# milligrids_v05_single_board.net
KiCad netlist of a schematic drawn in EAGLE
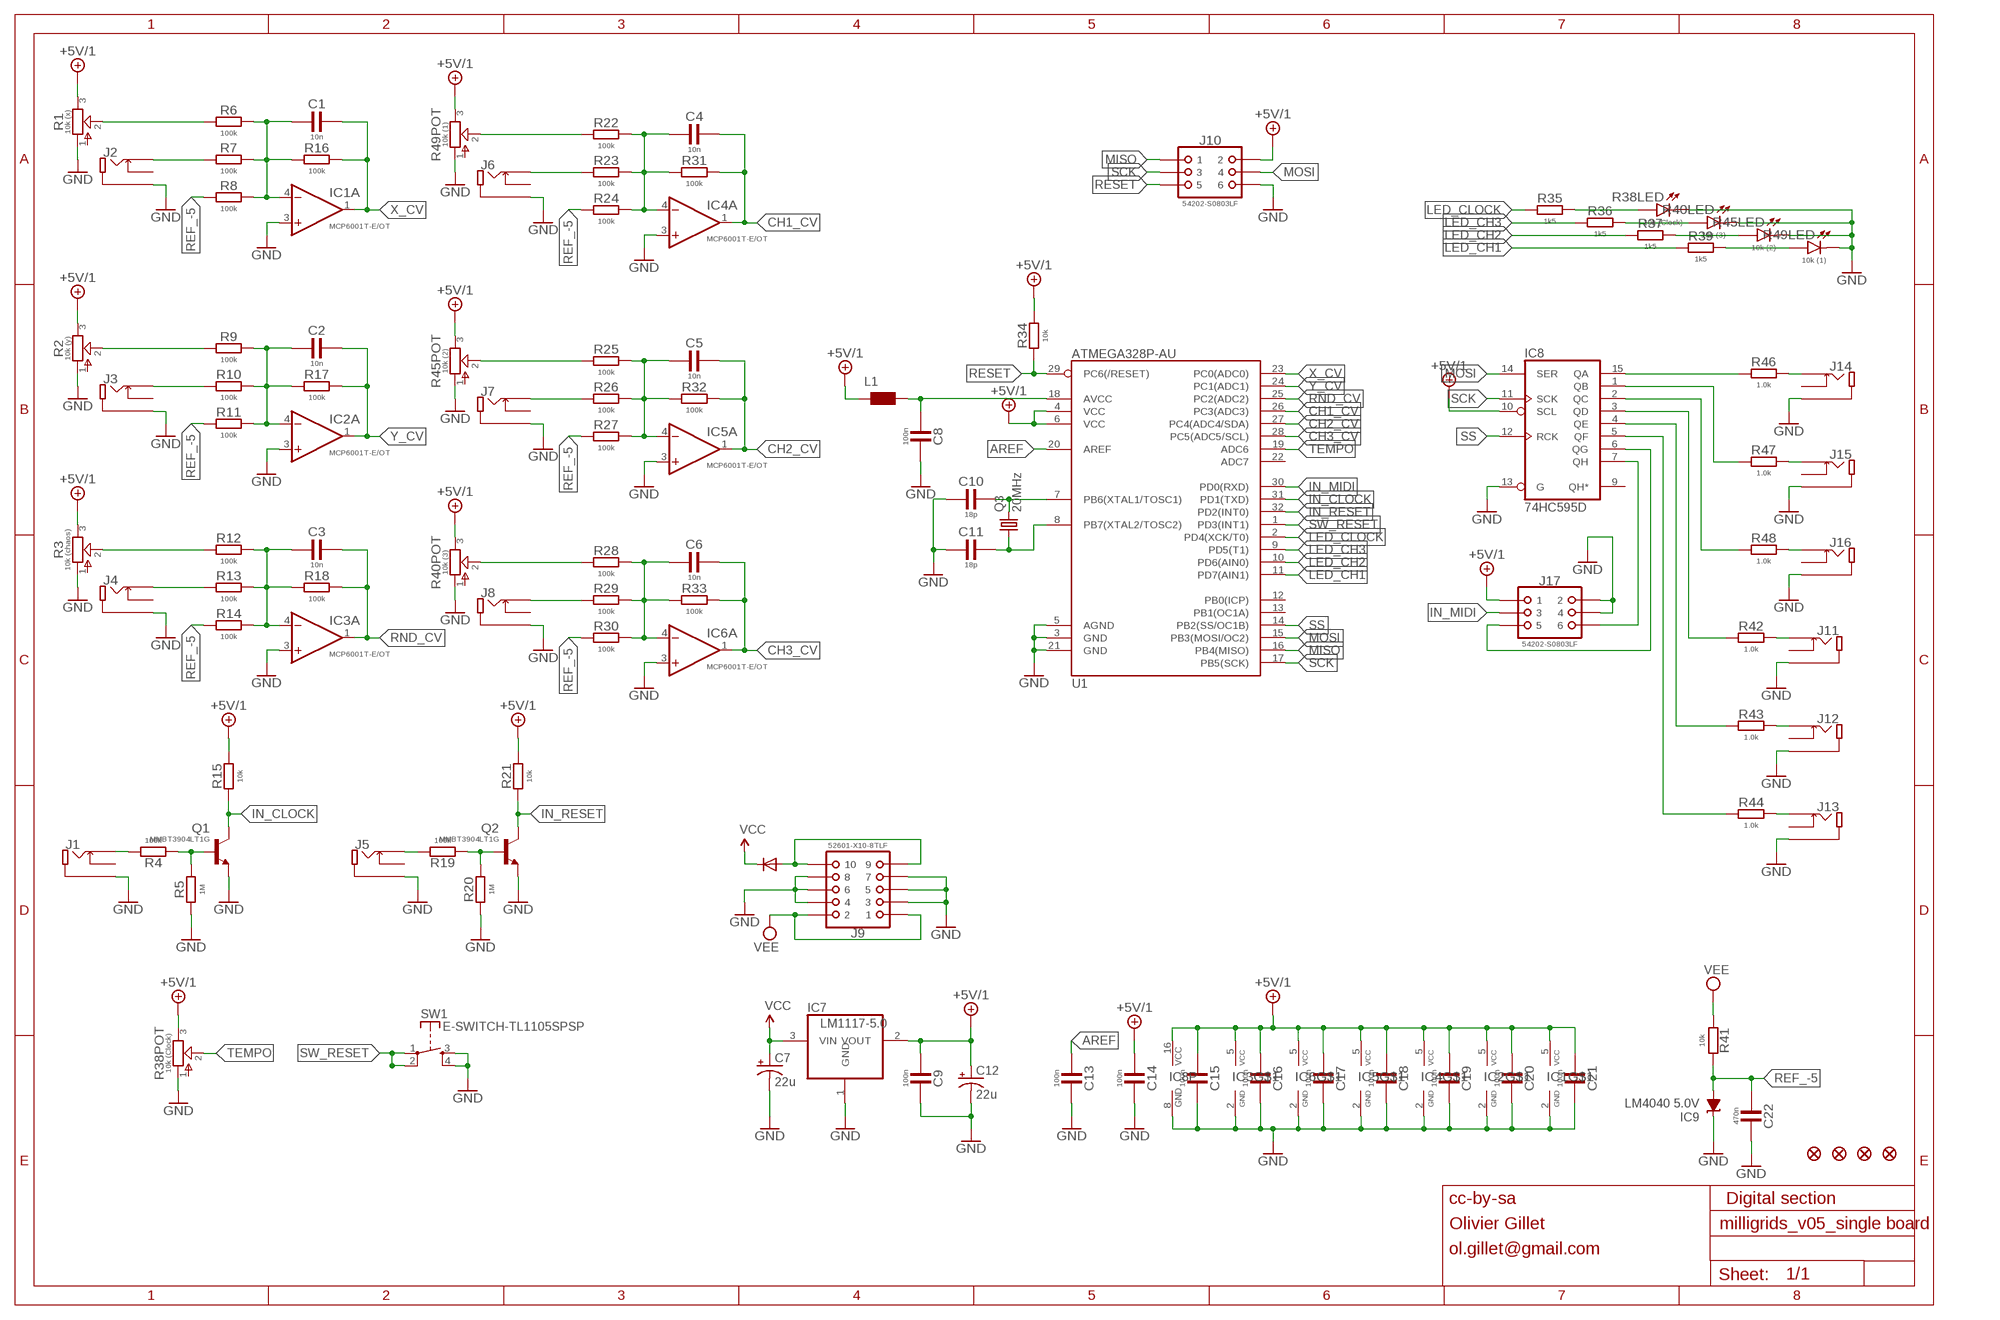
[diagram p0: schematic, sheet 1]

(export (version "E")
  (design (tool "Eeschema 10.0.6"))
  (components
    (comp (ref "C1")
      (value "10n")
      (footprint "eagle-import:C0805")
      (libsource (lib "eagle-import") (part "C0805"))
    )
    (comp (ref "C2")
      (value "10n")
      (footprint "eagle-import:C0805")
      (libsource (lib "eagle-import") (part "C0805"))
    )
    (comp (ref "C3")
      (value "10n")
      (footprint "eagle-import:C0805")
      (libsource (lib "eagle-import") (part "C0805"))
    )
    (comp (ref "C4")
      (value "10n")
      (footprint "eagle-import:C0603")
      (libsource (lib "eagle-import") (part "C0603"))
    )
    (comp (ref "C5")
      (value "10n")
      (footprint "eagle-import:C0603")
      (libsource (lib "eagle-import") (part "C0603"))
    )
    (comp (ref "C6")
      (value "10n")
      (footprint "eagle-import:C0603")
      (libsource (lib "eagle-import") (part "C0603"))
    )
    (comp (ref "C7")
      (value "22u")
      (footprint "eagle-import:PANASONIC_C")
      (libsource (lib "eagle-import") (part "CPOL-USC"))
    )
    (comp (ref "C8")
      (value "100n")
      (footprint "eagle-import:C0805")
      (libsource (lib "eagle-import") (part "C0805"))
    )
    (comp (ref "C9")
      (value "100n")
      (footprint "eagle-import:C0805")
      (libsource (lib "eagle-import") (part "C0805"))
    )
    (comp (ref "C10")
      (value "18p")
      (footprint "eagle-import:C0603")
      (libsource (lib "eagle-import") (part "C0603"))
    )
    (comp (ref "C11")
      (value "18p")
      (footprint "eagle-import:C0603")
      (libsource (lib "eagle-import") (part "C0603"))
    )
    (comp (ref "C12")
      (value "22u")
      (footprint "eagle-import:PANASONIC_C")
      (libsource (lib "eagle-import") (part "CPOL-USC"))
    )
    (comp (ref "C13")
      (value "100n")
      (footprint "eagle-import:C0805")
      (libsource (lib "eagle-import") (part "C0805"))
    )
    (comp (ref "C14")
      (value "100n")
      (footprint "eagle-import:C0805")
      (libsource (lib "eagle-import") (part "C0805"))
    )
    (comp (ref "C15")
      (value "100n")
      (footprint "eagle-import:C0805")
      (libsource (lib "eagle-import") (part "C0805"))
    )
    (comp (ref "C16")
      (value "100n")
      (footprint "eagle-import:C0805")
      (libsource (lib "eagle-import") (part "C0805"))
    )
    (comp (ref "C17")
      (value "100n")
      (footprint "eagle-import:C0805")
      (libsource (lib "eagle-import") (part "C0805"))
    )
    (comp (ref "C18")
      (value "100n")
      (footprint "eagle-import:C0805")
      (libsource (lib "eagle-import") (part "C0805"))
    )
    (comp (ref "C19")
      (value "100n")
      (footprint "eagle-import:C0805")
      (libsource (lib "eagle-import") (part "C0805"))
    )
    (comp (ref "C20")
      (value "100n")
      (footprint "eagle-import:C0805")
      (libsource (lib "eagle-import") (part "C0805"))
    )
    (comp (ref "C21")
      (value "100n")
      (footprint "eagle-import:C0805")
      (libsource (lib "eagle-import") (part "C0805"))
    )
    (comp (ref "C22")
      (value "470n")
      (footprint "eagle-import:C0805")
      (libsource (lib "eagle-import") (part "C0805"))
    )
    (comp (ref "D1")
      (value "1N5819HW")
      (footprint "eagle-import:SOD123")
      (libsource (lib "eagle-import") (part "DIODE-SOD123"))
    )
    (comp (ref "IC1")
      (value "MCP6001T-E/OT")
      (footprint "eagle-import:SOT23-5")
      (libsource (lib "eagle-import") (part "MCP6001T-E/OT"))
    )
    (comp (ref "IC2")
      (value "MCP6001T-E/OT")
      (footprint "eagle-import:SOT23-5")
      (libsource (lib "eagle-import") (part "MCP6001T-E/OT"))
    )
    (comp (ref "IC3")
      (value "MCP6001T-E/OT")
      (footprint "eagle-import:SOT23-5")
      (libsource (lib "eagle-import") (part "MCP6001T-E/OT"))
    )
    (comp (ref "IC4")
      (value "MCP6001T-E/OT")
      (footprint "eagle-import:SOT23-5")
      (libsource (lib "eagle-import") (part "MCP6001T-E/OT"))
    )
    (comp (ref "IC5")
      (value "MCP6001T-E/OT")
      (footprint "eagle-import:SOT23-5")
      (libsource (lib "eagle-import") (part "MCP6001T-E/OT"))
    )
    (comp (ref "IC6")
      (value "MCP6001T-E/OT")
      (footprint "eagle-import:SOT23-5")
      (libsource (lib "eagle-import") (part "MCP6001T-E/OT"))
    )
    (comp (ref "IC7")
      (value "LM1117-5.0")
      (footprint "eagle-import:SOT223")
      (libsource (lib "eagle-import") (part "REG1117"))
    )
    (comp (ref "IC8")
      (value "74HC595D")
      (footprint "eagle-import:SO16")
      (libsource (lib "eagle-import") (part "74595DHC"))
    )
    (comp (ref "IC9")
      (value "LM4040 5.0V")
      (footprint "eagle-import:DBZ_R-PDSO-G3")
      (libsource (lib "eagle-import") (part "LM4041DBZC12"))
    )
    (comp (ref "J1")
      (value "WQP-PJ301M6(THONKICONN)")
      (footprint "eagle-import:WQP-PJ301M6(THONKICONN)")
      (libsource (lib "eagle-import") (part "WQP-PJ301M6(THONKICONN)"))
    )
    (comp (ref "J2")
      (value "WQP-PJ301M6(THONKICONN)")
      (footprint "eagle-import:WQP-PJ301M6(THONKICONN)")
      (libsource (lib "eagle-import") (part "WQP-PJ301M6(THONKICONN)"))
    )
    (comp (ref "J3")
      (value "WQP-PJ301M6(THONKICONN)")
      (footprint "eagle-import:WQP-PJ301M6(THONKICONN)")
      (libsource (lib "eagle-import") (part "WQP-PJ301M6(THONKICONN)"))
    )
    (comp (ref "J4")
      (value "WQP-PJ301M6(THONKICONN)")
      (footprint "eagle-import:WQP-PJ301M6(THONKICONN)")
      (libsource (lib "eagle-import") (part "WQP-PJ301M6(THONKICONN)"))
    )
    (comp (ref "J5")
      (value "WQP-PJ301M6(THONKICONN)")
      (footprint "eagle-import:WQP-PJ301M6(THONKICONN)")
      (libsource (lib "eagle-import") (part "WQP-PJ301M6(THONKICONN)"))
    )
    (comp (ref "J6")
      (value "WQP-PJ301M6(THONKICONN)")
      (footprint "eagle-import:WQP-PJ301M6(THONKICONN)")
      (libsource (lib "eagle-import") (part "WQP-PJ301M6(THONKICONN)"))
    )
    (comp (ref "J7")
      (value "WQP-PJ301M6(THONKICONN)")
      (footprint "eagle-import:WQP-PJ301M6(THONKICONN)")
      (libsource (lib "eagle-import") (part "WQP-PJ301M6(THONKICONN)"))
    )
    (comp (ref "J8")
      (value "WQP-PJ301M6(THONKICONN)")
      (footprint "eagle-import:WQP-PJ301M6(THONKICONN)")
      (libsource (lib "eagle-import") (part "WQP-PJ301M6(THONKICONN)"))
    )
    (comp (ref "J9")
      (value "52601-X10-8TLF")
      (footprint "eagle-import:52601-(X)10-8TLF")
      (libsource (lib "eagle-import") (part "52601-X10-8TLF"))
    )
    (comp (ref "J10")
      (value "54202-S0803LF")
      (footprint "eagle-import:54202-S0803LF")
      (libsource (lib "eagle-import") (part "54202-S0803LF"))
    )
    (comp (ref "J11")
      (value "WQP-PJ301M6(THONKICONN)")
      (footprint "eagle-import:WQP-PJ301M6(THONKICONN)")
      (libsource (lib "eagle-import") (part "WQP-PJ301M6(THONKICONN)"))
    )
    (comp (ref "J12")
      (value "WQP-PJ301M6(THONKICONN)")
      (footprint "eagle-import:WQP-PJ301M6(THONKICONN)")
      (libsource (lib "eagle-import") (part "WQP-PJ301M6(THONKICONN)"))
    )
    (comp (ref "J13")
      (value "WQP-PJ301M6(THONKICONN)")
      (footprint "eagle-import:WQP-PJ301M6(THONKICONN)")
      (libsource (lib "eagle-import") (part "WQP-PJ301M6(THONKICONN)"))
    )
    (comp (ref "J14")
      (value "WQP-PJ301M6(THONKICONN)")
      (footprint "eagle-import:WQP-PJ301M6(THONKICONN)")
      (libsource (lib "eagle-import") (part "WQP-PJ301M6(THONKICONN)"))
    )
    (comp (ref "J15")
      (value "WQP-PJ301M6(THONKICONN)")
      (footprint "eagle-import:WQP-PJ301M6(THONKICONN)")
      (libsource (lib "eagle-import") (part "WQP-PJ301M6(THONKICONN)"))
    )
    (comp (ref "J16")
      (value "WQP-PJ301M6(THONKICONN)")
      (footprint "eagle-import:WQP-PJ301M6(THONKICONN)")
      (libsource (lib "eagle-import") (part "WQP-PJ301M6(THONKICONN)"))
    )
    (comp (ref "J17")
      (value "54202-S0803LF")
      (footprint "eagle-import:54202-S0803LF")
      (libsource (lib "eagle-import") (part "54202-S0803LF"))
    )
    (comp (ref "JP2")
      (value "FIDUCIAL1X2")
      (footprint "eagle-import:FIDUCIAL-1X2")
      (libsource (lib "eagle-import") (part "FIDUCIAL1X2"))
    )
    (comp (ref "JP3")
      (value "FIDUCIAL1X2")
      (footprint "eagle-import:FIDUCIAL-1X2")
      (libsource (lib "eagle-import") (part "FIDUCIAL1X2"))
    )
    (comp (ref "JP4")
      (value "FIDUCIAL1X2")
      (footprint "eagle-import:FIDUCIAL-1X2")
      (libsource (lib "eagle-import") (part "FIDUCIAL1X2"))
    )
    (comp (ref "JP5")
      (value "FIDUCIAL1X2")
      (footprint "eagle-import:FIDUCIAL-1X2")
      (libsource (lib "eagle-import") (part "FIDUCIAL1X2"))
    )
    (comp (ref "L1")
      (value "WE-CBF_0603")
      (footprint "eagle-import:0603")
      (libsource (lib "eagle-import") (part "WE-CBF_0603"))
    )
    (comp (ref "Q1")
      (value "MMBT3904LT1G")
      (footprint "eagle-import:SOT23-3")
      (libsource (lib "eagle-import") (part "MMBT3904LT1G"))
    )
    (comp (ref "Q2")
      (value "MMBT3904LT1G")
      (footprint "eagle-import:SOT23-3")
      (libsource (lib "eagle-import") (part "MMBT3904LT1G"))
    )
    (comp (ref "Q3")
      (value "20MHz")
      (footprint "eagle-import:HC49UP")
      (libsource (lib "eagle-import") (part "CRYSTALHC49UP"))
    )
    (comp (ref "R1")
      (value "10k (x)")
      (footprint "eagle-import:SONGHUEI-RK0914")
      (libsource (lib "eagle-import") (part "SONGHUEI-RK0914"))
    )
    (comp (ref "R2")
      (value "10k (y)")
      (footprint "eagle-import:SONGHUEI-RK0914")
      (libsource (lib "eagle-import") (part "SONGHUEI-RK0914"))
    )
    (comp (ref "R3")
      (value "10k (chaos)")
      (footprint "eagle-import:SONGHUEI-RK0914")
      (libsource (lib "eagle-import") (part "SONGHUEI-RK0914"))
    )
    (comp (ref "R4")
      (value "100k")
      (footprint "eagle-import:R0603")
      (libsource (lib "eagle-import") (part "R0603"))
    )
    (comp (ref "R5")
      (value "1M")
      (footprint "eagle-import:R0603")
      (libsource (lib "eagle-import") (part "R0603"))
    )
    (comp (ref "R6")
      (value "100k")
      (footprint "eagle-import:R0603")
      (libsource (lib "eagle-import") (part "R0603"))
    )
    (comp (ref "R7")
      (value "100k")
      (footprint "eagle-import:R0603")
      (libsource (lib "eagle-import") (part "R0603"))
    )
    (comp (ref "R8")
      (value "100k")
      (footprint "eagle-import:R0603")
      (libsource (lib "eagle-import") (part "R0603"))
    )
    (comp (ref "R9")
      (value "100k")
      (footprint "eagle-import:R0603")
      (libsource (lib "eagle-import") (part "R0603"))
    )
    (comp (ref "R10")
      (value "100k")
      (footprint "eagle-import:R0603")
      (libsource (lib "eagle-import") (part "R0603"))
    )
    (comp (ref "R11")
      (value "100k")
      (footprint "eagle-import:R0603")
      (libsource (lib "eagle-import") (part "R0603"))
    )
    (comp (ref "R12")
      (value "100k")
      (footprint "eagle-import:R0603")
      (libsource (lib "eagle-import") (part "R0603"))
    )
    (comp (ref "R13")
      (value "100k")
      (footprint "eagle-import:R0603")
      (libsource (lib "eagle-import") (part "R0603"))
    )
    (comp (ref "R14")
      (value "100k")
      (footprint "eagle-import:R0603")
      (libsource (lib "eagle-import") (part "R0603"))
    )
    (comp (ref "R15")
      (value "10k")
      (footprint "eagle-import:R0805")
      (libsource (lib "eagle-import") (part "R0805"))
    )
    (comp (ref "R16")
      (value "100k")
      (footprint "eagle-import:R0603")
      (libsource (lib "eagle-import") (part "R0603"))
    )
    (comp (ref "R17")
      (value "100k")
      (footprint "eagle-import:R0603")
      (libsource (lib "eagle-import") (part "R0603"))
    )
    (comp (ref "R18")
      (value "100k")
      (footprint "eagle-import:R0603")
      (libsource (lib "eagle-import") (part "R0603"))
    )
    (comp (ref "R19")
      (value "100k")
      (footprint "eagle-import:R0603")
      (libsource (lib "eagle-import") (part "R0603"))
    )
    (comp (ref "R20")
      (value "1M")
      (footprint "eagle-import:R0603")
      (libsource (lib "eagle-import") (part "R0603"))
    )
    (comp (ref "R21")
      (value "10k")
      (footprint "eagle-import:R0805")
      (libsource (lib "eagle-import") (part "R0805"))
    )
    (comp (ref "R22")
      (value "100k")
      (footprint "eagle-import:R0603")
      (libsource (lib "eagle-import") (part "R0603"))
    )
    (comp (ref "R23")
      (value "100k")
      (footprint "eagle-import:R0603")
      (libsource (lib "eagle-import") (part "R0603"))
    )
    (comp (ref "R24")
      (value "100k")
      (footprint "eagle-import:R0603")
      (libsource (lib "eagle-import") (part "R0603"))
    )
    (comp (ref "R25")
      (value "100k")
      (footprint "eagle-import:R0603")
      (libsource (lib "eagle-import") (part "R0603"))
    )
    (comp (ref "R26")
      (value "100k")
      (footprint "eagle-import:R0603")
      (libsource (lib "eagle-import") (part "R0603"))
    )
    (comp (ref "R27")
      (value "100k")
      (footprint "eagle-import:R0603")
      (libsource (lib "eagle-import") (part "R0603"))
    )
    (comp (ref "R28")
      (value "100k")
      (footprint "eagle-import:R0603")
      (libsource (lib "eagle-import") (part "R0603"))
    )
    (comp (ref "R29")
      (value "100k")
      (footprint "eagle-import:R0603")
      (libsource (lib "eagle-import") (part "R0603"))
    )
    (comp (ref "R30")
      (value "100k")
      (footprint "eagle-import:R0603")
      (libsource (lib "eagle-import") (part "R0603"))
    )
    (comp (ref "R31")
      (value "100k")
      (footprint "eagle-import:R0603")
      (libsource (lib "eagle-import") (part "R0603"))
    )
    (comp (ref "R32")
      (value "100k")
      (footprint "eagle-import:R0603")
      (libsource (lib "eagle-import") (part "R0603"))
    )
    (comp (ref "R33")
      (value "100k")
      (footprint "eagle-import:R0603")
      (libsource (lib "eagle-import") (part "R0603"))
    )
    (comp (ref "R34")
      (value "10k")
      (footprint "eagle-import:R0805")
      (libsource (lib "eagle-import") (part "R0805"))
    )
    (comp (ref "R35")
      (value "1k5")
      (footprint "eagle-import:R0805")
      (libsource (lib "eagle-import") (part "R0805"))
    )
    (comp (ref "R36")
      (value "1k5")
      (footprint "eagle-import:R0805")
      (libsource (lib "eagle-import") (part "R0805"))
    )
    (comp (ref "R37")
      (value "1k5")
      (footprint "eagle-import:R0805")
      (libsource (lib "eagle-import") (part "R0805"))
    )
    (comp (ref "R38")
      (value "10k (Clock)")
      (footprint "eagle-import:BOURNS-PTL30")
      (libsource (lib "eagle-import") (part "BOURNS-PTL30"))
    )
    (comp (ref "R39")
      (value "1k5")
      (footprint "eagle-import:R0805")
      (libsource (lib "eagle-import") (part "R0805"))
    )
    (comp (ref "R40")
      (value "10k (3)")
      (footprint "eagle-import:BOURNS-PTL30")
      (libsource (lib "eagle-import") (part "BOURNS-PTL30"))
    )
    (comp (ref "R41")
      (value "10k")
      (footprint "eagle-import:R0805")
      (libsource (lib "eagle-import") (part "R0805"))
    )
    (comp (ref "R42")
      (value "1.0k")
      (footprint "eagle-import:R0805")
      (libsource (lib "eagle-import") (part "R0805"))
    )
    (comp (ref "R43")
      (value "1.0k")
      (footprint "eagle-import:R0805")
      (libsource (lib "eagle-import") (part "R0805"))
    )
    (comp (ref "R44")
      (value "1.0k")
      (footprint "eagle-import:R0805")
      (libsource (lib "eagle-import") (part "R0805"))
    )
    (comp (ref "R45")
      (value "10k (2)")
      (footprint "eagle-import:BOURNS-PTL30")
      (libsource (lib "eagle-import") (part "BOURNS-PTL30"))
    )
    (comp (ref "R46")
      (value "1.0k")
      (footprint "eagle-import:R0805")
      (libsource (lib "eagle-import") (part "R0805"))
    )
    (comp (ref "R47")
      (value "1.0k")
      (footprint "eagle-import:R0805")
      (libsource (lib "eagle-import") (part "R0805"))
    )
    (comp (ref "R48")
      (value "1.0k")
      (footprint "eagle-import:R0805")
      (libsource (lib "eagle-import") (part "R0805"))
    )
    (comp (ref "R49")
      (value "10k (1)")
      (footprint "eagle-import:BOURNS-PTL30")
      (libsource (lib "eagle-import") (part "BOURNS-PTL30"))
    )
    (comp (ref "SW1")
      (value "E-SWITCH-TL1105SPSP")
      (footprint "eagle-import:E-SWITCH-TL1105SP")
      (libsource (lib "eagle-import") (part "E-SWITCH-TL1105SPSP"))
    )
    (comp (ref "U1")
      (value "ATMEGA328P-AU")
      (footprint "eagle-import:TQFP32-08")
      (libsource (lib "eagle-import") (part "ATMEGA168"))
    )
  )
  (nets
    (net (code "1") (name "+5V{slash}1") (class "Default")
      (node (ref "C12") (pin "+") (pinfunction "+_+") (pintype "passive"))
      (node (ref "C14") (pin "1") (pinfunction "1_1") (pintype "passive"))
      (node (ref "C15") (pin "1") (pinfunction "1_1") (pintype "passive"))
      (node (ref "C16") (pin "1") (pinfunction "1_1") (pintype "passive"))
      (node (ref "C17") (pin "1") (pinfunction "1_1") (pintype "passive"))
      (node (ref "C18") (pin "1") (pinfunction "1_1") (pintype "passive"))
      (node (ref "C19") (pin "1") (pinfunction "1_1") (pintype "passive"))
      (node (ref "C20") (pin "1") (pinfunction "1_1") (pintype "passive"))
      (node (ref "C21") (pin "1") (pinfunction "1_1") (pintype "passive"))
      (node (ref "C9") (pin "1") (pinfunction "1_1") (pintype "passive"))
      (node (ref "IC1") (pin "5") (pinfunction "VCC_5") (pintype "power_in"))
      (node (ref "IC2") (pin "5") (pinfunction "VCC_5") (pintype "power_in"))
      (node (ref "IC3") (pin "5") (pinfunction "VCC_5") (pintype "power_in"))
      (node (ref "IC4") (pin "5") (pinfunction "VCC_5") (pintype "power_in"))
      (node (ref "IC5") (pin "5") (pinfunction "VCC_5") (pintype "power_in"))
      (node (ref "IC6") (pin "5") (pinfunction "VCC_5") (pintype "power_in"))
      (node (ref "IC7") (pin "2") (pinfunction "VOUT_2") (pintype "output"))
      (node (ref "IC8") (pin "10") (pinfunction "SCL_10") (pintype "input"))
      (node (ref "IC8") (pin "16") (pinfunction "VCC_16") (pintype "power_in"))
      (node (ref "J10") (pin "2") (pinfunction "2_2") (pintype "passive"))
      (node (ref "J17") (pin "1") (pinfunction "1_1") (pintype "passive"))
      (node (ref "L1") (pin "1") (pinfunction "1_1") (pintype "passive"))
      (node (ref "R1") (pin "3") (pinfunction "3_3") (pintype "passive"))
      (node (ref "R15") (pin "2") (pinfunction "2_2") (pintype "passive"))
      (node (ref "R2") (pin "3") (pinfunction "3_3") (pintype "passive"))
      (node (ref "R21") (pin "2") (pinfunction "2_2") (pintype "passive"))
      (node (ref "R3") (pin "3") (pinfunction "3_3") (pintype "passive"))
      (node (ref "R34") (pin "2") (pinfunction "2_2") (pintype "passive"))
      (node (ref "R38") (pin "3") (pinfunction "3_3") (pintype "passive"))
      (node (ref "R40") (pin "3") (pinfunction "3_3") (pintype "passive"))
      (node (ref "R45") (pin "3") (pinfunction "3_3") (pintype "passive"))
      (node (ref "R49") (pin "3") (pinfunction "3_3") (pintype "passive"))
      (node (ref "U1") (pin "4") (pinfunction "VCC_4") (pintype "bidirectional"))
      (node (ref "U1") (pin "6") (pinfunction "VCC_6") (pintype "bidirectional"))
    )
    (net (code "2") (name "AREF") (class "Default")
      (node (ref "C13") (pin "1") (pinfunction "1_1") (pintype "passive"))
      (node (ref "U1") (pin "20") (pinfunction "AREF_20") (pintype "bidirectional"))
    )
    (net (code "3") (name "CH1_CV") (class "Default")
      (node (ref "C4") (pin "2") (pinfunction "2_2") (pintype "passive"))
      (node (ref "IC4") (pin "1") (pinfunction "OUT_1") (pintype "output"))
      (node (ref "R31") (pin "2") (pinfunction "2_2") (pintype "passive"))
      (node (ref "U1") (pin "26") (pinfunction "PC3(ADC3)_26") (pintype "bidirectional"))
    )
    (net (code "4") (name "CH2_CV") (class "Default")
      (node (ref "C5") (pin "2") (pinfunction "2_2") (pintype "passive"))
      (node (ref "IC5") (pin "1") (pinfunction "OUT_1") (pintype "output"))
      (node (ref "R32") (pin "2") (pinfunction "2_2") (pintype "passive"))
      (node (ref "U1") (pin "27") (pinfunction "PC4(ADC4/SDA)_27") (pintype "bidirectional"))
    )
    (net (code "5") (name "CH3_CV") (class "Default")
      (node (ref "C6") (pin "2") (pinfunction "2_2") (pintype "passive"))
      (node (ref "IC6") (pin "1") (pinfunction "OUT_1") (pintype "output"))
      (node (ref "R33") (pin "2") (pinfunction "2_2") (pintype "passive"))
      (node (ref "U1") (pin "28") (pinfunction "PC5(ADC5/SCL)_28") (pintype "bidirectional"))
    )
    (net (code "6") (name "GND") (class "Default")
      (node (ref "C10") (pin "1") (pinfunction "1_1") (pintype "passive"))
      (node (ref "C11") (pin "1") (pinfunction "1_1") (pintype "passive"))
      (node (ref "C12") (pin "-") (pinfunction "-_-") (pintype "passive"))
      (node (ref "C13") (pin "2") (pinfunction "2_2") (pintype "passive"))
      (node (ref "C14") (pin "2") (pinfunction "2_2") (pintype "passive"))
      (node (ref "C15") (pin "2") (pinfunction "2_2") (pintype "passive"))
      (node (ref "C16") (pin "2") (pinfunction "2_2") (pintype "passive"))
      (node (ref "C17") (pin "2") (pinfunction "2_2") (pintype "passive"))
      (node (ref "C18") (pin "2") (pinfunction "2_2") (pintype "passive"))
      (node (ref "C19") (pin "2") (pinfunction "2_2") (pintype "passive"))
      (node (ref "C20") (pin "2") (pinfunction "2_2") (pintype "passive"))
      (node (ref "C21") (pin "2") (pinfunction "2_2") (pintype "passive"))
      (node (ref "C22") (pin "2") (pinfunction "2_2") (pintype "passive"))
      (node (ref "C7") (pin "-") (pinfunction "-_-") (pintype "passive"))
      (node (ref "C8") (pin "2") (pinfunction "2_2") (pintype "passive"))
      (node (ref "C9") (pin "2") (pinfunction "2_2") (pintype "passive"))
      (node (ref "IC1") (pin "2") (pinfunction "GND_2") (pintype "power_in"))
      (node (ref "IC1") (pin "3") (pinfunction "+IN_3") (pintype "input"))
      (node (ref "IC2") (pin "2") (pinfunction "GND_2") (pintype "power_in"))
      (node (ref "IC2") (pin "3") (pinfunction "+IN_3") (pintype "input"))
      (node (ref "IC3") (pin "2") (pinfunction "GND_2") (pintype "power_in"))
      (node (ref "IC3") (pin "3") (pinfunction "+IN_3") (pintype "input"))
      (node (ref "IC4") (pin "2") (pinfunction "GND_2") (pintype "power_in"))
      (node (ref "IC4") (pin "3") (pinfunction "+IN_3") (pintype "input"))
      (node (ref "IC5") (pin "2") (pinfunction "GND_2") (pintype "power_in"))
      (node (ref "IC5") (pin "3") (pinfunction "+IN_3") (pintype "input"))
      (node (ref "IC6") (pin "2") (pinfunction "GND_2") (pintype "power_in"))
      (node (ref "IC6") (pin "3") (pinfunction "+IN_3") (pintype "input"))
      (node (ref "IC7") (pin "1") (pinfunction "GND_1") (pintype "power_in"))
      (node (ref "IC8") (pin "13") (pinfunction "G_13") (pintype "input"))
      (node (ref "IC8") (pin "8") (pinfunction "GND_8") (pintype "power_in"))
      (node (ref "IC9") (pin "1") (pinfunction "C_1") (pintype "passive"))
      (node (ref "J1") (pin "P1") (pinfunction "1_P1") (pintype "bidirectional"))
      (node (ref "J10") (pin "6") (pinfunction "6_6") (pintype "passive"))
      (node (ref "J11") (pin "P1") (pinfunction "1_P1") (pintype "bidirectional"))
      (node (ref "J12") (pin "P1") (pinfunction "1_P1") (pintype "bidirectional"))
      (node (ref "J13") (pin "P1") (pinfunction "1_P1") (pintype "bidirectional"))
      (node (ref "J14") (pin "P1") (pinfunction "1_P1") (pintype "bidirectional"))
      (node (ref "J15") (pin "P1") (pinfunction "1_P1") (pintype "bidirectional"))
      (node (ref "J16") (pin "P1") (pinfunction "1_P1") (pintype "bidirectional"))
      (node (ref "J17") (pin "2") (pinfunction "2_2") (pintype "passive"))
      (node (ref "J17") (pin "4") (pinfunction "4_4") (pintype "passive"))
      (node (ref "J2") (pin "P1") (pinfunction "1_P1") (pintype "bidirectional"))
      (node (ref "J3") (pin "P1") (pinfunction "1_P1") (pintype "bidirectional"))
      (node (ref "J4") (pin "P1") (pinfunction "1_P1") (pintype "bidirectional"))
      (node (ref "J5") (pin "P1") (pinfunction "1_P1") (pintype "bidirectional"))
      (node (ref "J6") (pin "P1") (pinfunction "1_P1") (pintype "bidirectional"))
      (node (ref "J7") (pin "P1") (pinfunction "1_P1") (pintype "bidirectional"))
      (node (ref "J8") (pin "P1") (pinfunction "1_P1") (pintype "bidirectional"))
      (node (ref "J9") (pin "3") (pinfunction "3_3") (pintype "passive"))
      (node (ref "J9") (pin "4") (pinfunction "4_4") (pintype "passive"))
      (node (ref "J9") (pin "5") (pinfunction "5_5") (pintype "passive"))
      (node (ref "J9") (pin "6") (pinfunction "6_6") (pintype "passive"))
      (node (ref "J9") (pin "7") (pinfunction "7_7") (pintype "passive"))
      (node (ref "J9") (pin "8") (pinfunction "8_8") (pintype "passive"))
      (node (ref "Q1") (pin "2") (pinfunction "E_2") (pintype "passive"))
      (node (ref "Q2") (pin "2") (pinfunction "E_2") (pintype "passive"))
      (node (ref "R1") (pin "1") (pinfunction "1_1") (pintype "passive"))
      (node (ref "R2") (pin "1") (pinfunction "1_1") (pintype "passive"))
      (node (ref "R20") (pin "1") (pinfunction "1_1") (pintype "passive"))
      (node (ref "R3") (pin "1") (pinfunction "1_1") (pintype "passive"))
      (node (ref "R38") (pin "1") (pinfunction "1_1") (pintype "passive"))
      (node (ref "R38") (pin "E") (pinfunction "K_E") (pintype "passive"))
      (node (ref "R40") (pin "1") (pinfunction "1_1") (pintype "passive"))
      (node (ref "R40") (pin "E") (pinfunction "K_E") (pintype "passive"))
      (node (ref "R45") (pin "1") (pinfunction "1_1") (pintype "passive"))
      (node (ref "R45") (pin "E") (pinfunction "K_E") (pintype "passive"))
      (node (ref "R49") (pin "1") (pinfunction "1_1") (pintype "passive"))
      (node (ref "R49") (pin "E") (pinfunction "K_E") (pintype "passive"))
      (node (ref "R5") (pin "1") (pinfunction "1_1") (pintype "passive"))
      (node (ref "SW1") (pin "3") (pinfunction "3_3") (pintype "passive"))
      (node (ref "SW1") (pin "4") (pinfunction "4_4") (pintype "passive"))
      (node (ref "U1") (pin "21") (pinfunction "GND_21") (pintype "bidirectional"))
      (node (ref "U1") (pin "3") (pinfunction "GND_3") (pintype "bidirectional"))
      (node (ref "U1") (pin "5") (pinfunction "AGND_5") (pintype "bidirectional"))
    )
    (net (code "7") (name "IN_CLOCK") (class "Default")
      (node (ref "Q1") (pin "3") (pinfunction "C_3") (pintype "passive"))
      (node (ref "R15") (pin "1") (pinfunction "1_1") (pintype "passive"))
      (node (ref "U1") (pin "31") (pinfunction "PD1(TXD)_31") (pintype "bidirectional"))
    )
    (net (code "8") (name "IN_MIDI") (class "Default")
      (node (ref "J17") (pin "3") (pinfunction "3_3") (pintype "passive"))
      (node (ref "U1") (pin "30") (pinfunction "PD0(RXD)_30") (pintype "bidirectional"))
    )
    (net (code "9") (name "IN_RESET") (class "Default")
      (node (ref "Q2") (pin "3") (pinfunction "C_3") (pintype "passive"))
      (node (ref "R21") (pin "1") (pinfunction "1_1") (pintype "passive"))
      (node (ref "U1") (pin "32") (pinfunction "PD2(INT0)_32") (pintype "bidirectional"))
    )
    (net (code "10") (name "LED_CH1") (class "Default")
      (node (ref "R39") (pin "1") (pinfunction "1_1") (pintype "passive"))
      (node (ref "U1") (pin "11") (pinfunction "PD7(AIN1)_11") (pintype "bidirectional"))
    )
    (net (code "11") (name "LED_CH2") (class "Default")
      (node (ref "R37") (pin "1") (pinfunction "1_1") (pintype "passive"))
      (node (ref "U1") (pin "10") (pinfunction "PD6(AIN0)_10") (pintype "bidirectional"))
    )
    (net (code "12") (name "LED_CH3") (class "Default")
      (node (ref "R36") (pin "1") (pinfunction "1_1") (pintype "passive"))
      (node (ref "U1") (pin "9") (pinfunction "PD5(T1)_9") (pintype "bidirectional"))
    )
    (net (code "13") (name "LED_CLOCK") (class "Default")
      (node (ref "R35") (pin "1") (pinfunction "1_1") (pintype "passive"))
      (node (ref "U1") (pin "2") (pinfunction "PD4(XCK/T0)_2") (pintype "bidirectional"))
    )
    (net (code "14") (name "MISO") (class "Default")
      (node (ref "J10") (pin "1") (pinfunction "1_1") (pintype "passive"))
      (node (ref "U1") (pin "16") (pinfunction "PB4(MISO)_16") (pintype "bidirectional"))
    )
    (net (code "15") (name "MOSI") (class "Default")
      (node (ref "IC8") (pin "14") (pinfunction "SER_14") (pintype "input"))
      (node (ref "J10") (pin "4") (pinfunction "4_4") (pintype "passive"))
      (node (ref "U1") (pin "15") (pinfunction "PB3(MOSI/OC2)_15") (pintype "bidirectional"))
    )
    (net (code "16") (name "Net-(D1-PadA)") (class "Default")
      (node (ref "D1") (pin "A") (pinfunction "A_A") (pintype "passive"))
      (node (ref "J9") (pin "10") (pinfunction "10_10") (pintype "passive"))
      (node (ref "J9") (pin "9") (pinfunction "9_9") (pintype "passive"))
    )
    (net (code "17") (name "Net-(IC1A--IN)") (class "Default")
      (node (ref "C1") (pin "1") (pinfunction "1_1") (pintype "passive"))
      (node (ref "IC1") (pin "4") (pinfunction "-IN_4") (pintype "input"))
      (node (ref "R16") (pin "1") (pinfunction "1_1") (pintype "passive"))
      (node (ref "R6") (pin "2") (pinfunction "2_2") (pintype "passive"))
      (node (ref "R7") (pin "2") (pinfunction "2_2") (pintype "passive"))
      (node (ref "R8") (pin "2") (pinfunction "2_2") (pintype "passive"))
    )
    (net (code "18") (name "Net-(IC2A--IN)") (class "Default")
      (node (ref "C2") (pin "1") (pinfunction "1_1") (pintype "passive"))
      (node (ref "IC2") (pin "4") (pinfunction "-IN_4") (pintype "input"))
      (node (ref "R10") (pin "2") (pinfunction "2_2") (pintype "passive"))
      (node (ref "R11") (pin "2") (pinfunction "2_2") (pintype "passive"))
      (node (ref "R17") (pin "1") (pinfunction "1_1") (pintype "passive"))
      (node (ref "R9") (pin "2") (pinfunction "2_2") (pintype "passive"))
    )
    (net (code "19") (name "Net-(IC3A--IN)") (class "Default")
      (node (ref "C3") (pin "1") (pinfunction "1_1") (pintype "passive"))
      (node (ref "IC3") (pin "4") (pinfunction "-IN_4") (pintype "input"))
      (node (ref "R12") (pin "2") (pinfunction "2_2") (pintype "passive"))
      (node (ref "R13") (pin "2") (pinfunction "2_2") (pintype "passive"))
      (node (ref "R14") (pin "2") (pinfunction "2_2") (pintype "passive"))
      (node (ref "R18") (pin "1") (pinfunction "1_1") (pintype "passive"))
    )
    (net (code "20") (name "Net-(IC4A--IN)") (class "Default")
      (node (ref "C4") (pin "1") (pinfunction "1_1") (pintype "passive"))
      (node (ref "IC4") (pin "4") (pinfunction "-IN_4") (pintype "input"))
      (node (ref "R22") (pin "2") (pinfunction "2_2") (pintype "passive"))
      (node (ref "R23") (pin "2") (pinfunction "2_2") (pintype "passive"))
      (node (ref "R24") (pin "2") (pinfunction "2_2") (pintype "passive"))
      (node (ref "R31") (pin "1") (pinfunction "1_1") (pintype "passive"))
    )
    (net (code "21") (name "Net-(IC5A--IN)") (class "Default")
      (node (ref "C5") (pin "1") (pinfunction "1_1") (pintype "passive"))
      (node (ref "IC5") (pin "4") (pinfunction "-IN_4") (pintype "input"))
      (node (ref "R25") (pin "2") (pinfunction "2_2") (pintype "passive"))
      (node (ref "R26") (pin "2") (pinfunction "2_2") (pintype "passive"))
      (node (ref "R27") (pin "2") (pinfunction "2_2") (pintype "passive"))
      (node (ref "R32") (pin "1") (pinfunction "1_1") (pintype "passive"))
    )
    (net (code "22") (name "Net-(IC6A--IN)") (class "Default")
      (node (ref "C6") (pin "1") (pinfunction "1_1") (pintype "passive"))
      (node (ref "IC6") (pin "4") (pinfunction "-IN_4") (pintype "input"))
      (node (ref "R28") (pin "2") (pinfunction "2_2") (pintype "passive"))
      (node (ref "R29") (pin "2") (pinfunction "2_2") (pintype "passive"))
      (node (ref "R30") (pin "2") (pinfunction "2_2") (pintype "passive"))
      (node (ref "R33") (pin "1") (pinfunction "1_1") (pintype "passive"))
    )
    (net (code "23") (name "Net-(IC8A-QA)") (class "Default")
      (node (ref "IC8") (pin "15") (pinfunction "QA_15") (pintype "tri_state"))
      (node (ref "R46") (pin "1") (pinfunction "1_1") (pintype "passive"))
    )
    (net (code "24") (name "Net-(IC8A-QB)") (class "Default")
      (node (ref "IC8") (pin "1") (pinfunction "QB_1") (pintype "tri_state"))
      (node (ref "R47") (pin "1") (pinfunction "1_1") (pintype "passive"))
    )
    (net (code "25") (name "Net-(IC8A-QC)") (class "Default")
      (node (ref "IC8") (pin "2") (pinfunction "QC_2") (pintype "tri_state"))
      (node (ref "R48") (pin "1") (pinfunction "1_1") (pintype "passive"))
    )
    (net (code "26") (name "Net-(IC8A-QD)") (class "Default")
      (node (ref "IC8") (pin "3") (pinfunction "QD_3") (pintype "tri_state"))
      (node (ref "R42") (pin "1") (pinfunction "1_1") (pintype "passive"))
    )
    (net (code "27") (name "Net-(IC8A-QE)") (class "Default")
      (node (ref "IC8") (pin "4") (pinfunction "QE_4") (pintype "tri_state"))
      (node (ref "R43") (pin "1") (pinfunction "1_1") (pintype "passive"))
    )
    (net (code "28") (name "Net-(IC8A-QF)") (class "Default")
      (node (ref "IC8") (pin "5") (pinfunction "QF_5") (pintype "tri_state"))
      (node (ref "R44") (pin "1") (pinfunction "1_1") (pintype "passive"))
    )
    (net (code "29") (name "Net-(IC8A-QG)") (class "Default")
      (node (ref "IC8") (pin "6") (pinfunction "QG_6") (pintype "tri_state"))
      (node (ref "J17") (pin "5") (pinfunction "5_5") (pintype "passive"))
    )
    (net (code "30") (name "Net-(IC8A-QH)") (class "Default")
      (node (ref "IC8") (pin "7") (pinfunction "QH_7") (pintype "tri_state"))
      (node (ref "J17") (pin "6") (pinfunction "6_6") (pintype "passive"))
    )
    (net (code "31") (name "Net-(J1-3)") (class "Default")
      (node (ref "J1") (pin "P3") (pinfunction "3_P3") (pintype "bidirectional"))
      (node (ref "R4") (pin "2") (pinfunction "2_2") (pintype "passive"))
    )
    (net (code "32") (name "Net-(J2-3)") (class "Default")
      (node (ref "J2") (pin "P3") (pinfunction "3_P3") (pintype "bidirectional"))
      (node (ref "R7") (pin "1") (pinfunction "1_1") (pintype "passive"))
    )
    (net (code "33") (name "Net-(J3-3)") (class "Default")
      (node (ref "J3") (pin "P3") (pinfunction "3_P3") (pintype "bidirectional"))
      (node (ref "R10") (pin "1") (pinfunction "1_1") (pintype "passive"))
    )
    (net (code "34") (name "Net-(J4-3)") (class "Default")
      (node (ref "J4") (pin "P3") (pinfunction "3_P3") (pintype "bidirectional"))
      (node (ref "R13") (pin "1") (pinfunction "1_1") (pintype "passive"))
    )
    (net (code "35") (name "Net-(J5-3)") (class "Default")
      (node (ref "J5") (pin "P3") (pinfunction "3_P3") (pintype "bidirectional"))
      (node (ref "R19") (pin "2") (pinfunction "2_2") (pintype "passive"))
    )
    (net (code "36") (name "Net-(J6-3)") (class "Default")
      (node (ref "J6") (pin "P3") (pinfunction "3_P3") (pintype "bidirectional"))
      (node (ref "R23") (pin "1") (pinfunction "1_1") (pintype "passive"))
    )
    (net (code "37") (name "Net-(J7-3)") (class "Default")
      (node (ref "J7") (pin "P3") (pinfunction "3_P3") (pintype "bidirectional"))
      (node (ref "R26") (pin "1") (pinfunction "1_1") (pintype "passive"))
    )
    (net (code "38") (name "Net-(J8-3)") (class "Default")
      (node (ref "J8") (pin "P3") (pinfunction "3_P3") (pintype "bidirectional"))
      (node (ref "R29") (pin "1") (pinfunction "1_1") (pintype "passive"))
    )
    (net (code "39") (name "Net-(J11-3)") (class "Default")
      (node (ref "J11") (pin "P3") (pinfunction "3_P3") (pintype "bidirectional"))
      (node (ref "R42") (pin "2") (pinfunction "2_2") (pintype "passive"))
    )
    (net (code "40") (name "Net-(J12-3)") (class "Default")
      (node (ref "J12") (pin "P3") (pinfunction "3_P3") (pintype "bidirectional"))
      (node (ref "R43") (pin "2") (pinfunction "2_2") (pintype "passive"))
    )
    (net (code "41") (name "Net-(J13-3)") (class "Default")
      (node (ref "J13") (pin "P3") (pinfunction "3_P3") (pintype "bidirectional"))
      (node (ref "R44") (pin "2") (pinfunction "2_2") (pintype "passive"))
    )
    (net (code "42") (name "Net-(J14-3)") (class "Default")
      (node (ref "J14") (pin "P3") (pinfunction "3_P3") (pintype "bidirectional"))
      (node (ref "R46") (pin "2") (pinfunction "2_2") (pintype "passive"))
    )
    (net (code "43") (name "Net-(J15-3)") (class "Default")
      (node (ref "J15") (pin "P3") (pinfunction "3_P3") (pintype "bidirectional"))
      (node (ref "R47") (pin "2") (pinfunction "2_2") (pintype "passive"))
    )
    (net (code "44") (name "Net-(J16-3)") (class "Default")
      (node (ref "J16") (pin "P3") (pinfunction "3_P3") (pintype "bidirectional"))
      (node (ref "R48") (pin "2") (pinfunction "2_2") (pintype "passive"))
    )
    (net (code "45") (name "Net-(Q1-B)") (class "Default")
      (node (ref "Q1") (pin "1") (pinfunction "B_1") (pintype "passive"))
      (node (ref "R4") (pin "1") (pinfunction "1_1") (pintype "passive"))
      (node (ref "R5") (pin "2") (pinfunction "2_2") (pintype "passive"))
    )
    (net (code "46") (name "Net-(Q2-B)") (class "Default")
      (node (ref "Q2") (pin "1") (pinfunction "B_1") (pintype "passive"))
      (node (ref "R19") (pin "1") (pinfunction "1_1") (pintype "passive"))
      (node (ref "R20") (pin "2") (pinfunction "2_2") (pintype "passive"))
    )
    (net (code "47") (name "Net-(R1-Pad2)") (class "Default")
      (node (ref "R1") (pin "2") (pinfunction "2_2") (pintype "passive"))
      (node (ref "R6") (pin "1") (pinfunction "1_1") (pintype "passive"))
    )
    (net (code "48") (name "Net-(R2-Pad2)") (class "Default")
      (node (ref "R2") (pin "2") (pinfunction "2_2") (pintype "passive"))
      (node (ref "R9") (pin "1") (pinfunction "1_1") (pintype "passive"))
    )
    (net (code "49") (name "Net-(R12-Pad1)") (class "Default")
      (node (ref "R12") (pin "1") (pinfunction "1_1") (pintype "passive"))
      (node (ref "R3") (pin "2") (pinfunction "2_2") (pintype "passive"))
    )
    (net (code "50") (name "Net-(R22-Pad1)") (class "Default")
      (node (ref "R22") (pin "1") (pinfunction "1_1") (pintype "passive"))
      (node (ref "R49") (pin "2") (pinfunction "2_2") (pintype "passive"))
    )
    (net (code "51") (name "Net-(R25-Pad1)") (class "Default")
      (node (ref "R25") (pin "1") (pinfunction "1_1") (pintype "passive"))
      (node (ref "R45") (pin "2") (pinfunction "2_2") (pintype "passive"))
    )
    (net (code "52") (name "Net-(R28-Pad1)") (class "Default")
      (node (ref "R28") (pin "1") (pinfunction "1_1") (pintype "passive"))
      (node (ref "R40") (pin "2") (pinfunction "2_2") (pintype "passive"))
    )
    (net (code "53") (name "Net-(R38A-A)") (class "Default")
      (node (ref "R35") (pin "2") (pinfunction "2_2") (pintype "passive"))
      (node (ref "R38") (pin "B") (pinfunction "A_B") (pintype "passive"))
    )
    (net (code "54") (name "Net-(R40A-A)") (class "Default")
      (node (ref "R36") (pin "2") (pinfunction "2_2") (pintype "passive"))
      (node (ref "R40") (pin "B") (pinfunction "A_B") (pintype "passive"))
    )
    (net (code "55") (name "Net-(R45A-A)") (class "Default")
      (node (ref "R37") (pin "2") (pinfunction "2_2") (pintype "passive"))
      (node (ref "R45") (pin "B") (pinfunction "A_B") (pintype "passive"))
    )
    (net (code "56") (name "Net-(R49A-A)") (class "Default")
      (node (ref "R39") (pin "2") (pinfunction "2_2") (pintype "passive"))
      (node (ref "R49") (pin "B") (pinfunction "A_B") (pintype "passive"))
    )
    (net (code "57") (name "Net-(U1-AVCC)") (class "Default")
      (node (ref "C8") (pin "1") (pinfunction "1_1") (pintype "passive"))
      (node (ref "L1") (pin "2") (pinfunction "2_2") (pintype "passive"))
      (node (ref "U1") (pin "18") (pinfunction "AVCC_18") (pintype "bidirectional"))
    )
    (net (code "58") (name "Net-(U1-PB6(XTAL1{slash}TOSC1))") (class "Default")
      (node (ref "C10") (pin "2") (pinfunction "2_2") (pintype "passive"))
      (node (ref "Q3") (pin "2") (pinfunction "2_2") (pintype "passive"))
      (node (ref "U1") (pin "7") (pinfunction "PB6(XTAL1/TOSC1)_7") (pintype "bidirectional"))
    )
    (net (code "59") (name "Net-(U1-PB7(XTAL2{slash}TOSC2))") (class "Default")
      (node (ref "C11") (pin "2") (pinfunction "2_2") (pintype "passive"))
      (node (ref "Q3") (pin "1") (pinfunction "1_1") (pintype "passive"))
      (node (ref "U1") (pin "8") (pinfunction "PB7(XTAL2/TOSC2)_8") (pintype "bidirectional"))
    )
    (net (code "60") (name "REF_-5") (class "Default")
      (node (ref "C22") (pin "1") (pinfunction "1_1") (pintype "passive"))
      (node (ref "IC9") (pin "2") (pinfunction "A_2") (pintype "passive"))
      (node (ref "R11") (pin "1") (pinfunction "1_1") (pintype "passive"))
      (node (ref "R14") (pin "1") (pinfunction "1_1") (pintype "passive"))
      (node (ref "R24") (pin "1") (pinfunction "1_1") (pintype "passive"))
      (node (ref "R27") (pin "1") (pinfunction "1_1") (pintype "passive"))
      (node (ref "R30") (pin "1") (pinfunction "1_1") (pintype "passive"))
      (node (ref "R41") (pin "2") (pinfunction "2_2") (pintype "passive"))
      (node (ref "R8") (pin "1") (pinfunction "1_1") (pintype "passive"))
    )
    (net (code "61") (name "RESET") (class "Default")
      (node (ref "J10") (pin "5") (pinfunction "5_5") (pintype "passive"))
      (node (ref "R34") (pin "1") (pinfunction "1_1") (pintype "passive"))
      (node (ref "U1") (pin "29") (pinfunction "PC6(/RESET)_29") (pintype "bidirectional"))
    )
    (net (code "62") (name "RND_CV") (class "Default")
      (node (ref "C3") (pin "2") (pinfunction "2_2") (pintype "passive"))
      (node (ref "IC3") (pin "1") (pinfunction "OUT_1") (pintype "output"))
      (node (ref "R18") (pin "2") (pinfunction "2_2") (pintype "passive"))
      (node (ref "U1") (pin "25") (pinfunction "PC2(ADC2)_25") (pintype "bidirectional"))
    )
    (net (code "63") (name "SCK") (class "Default")
      (node (ref "IC8") (pin "11") (pinfunction "SCK_11") (pintype "input"))
      (node (ref "J10") (pin "3") (pinfunction "3_3") (pintype "passive"))
      (node (ref "U1") (pin "17") (pinfunction "PB5(SCK)_17") (pintype "bidirectional"))
    )
    (net (code "64") (name "SS") (class "Default")
      (node (ref "IC8") (pin "12") (pinfunction "RCK_12") (pintype "input"))
      (node (ref "U1") (pin "14") (pinfunction "PB2(SS/OC1B)_14") (pintype "bidirectional"))
    )
    (net (code "65") (name "SW_RESET") (class "Default")
      (node (ref "SW1") (pin "1") (pinfunction "1_1") (pintype "passive"))
      (node (ref "SW1") (pin "2") (pinfunction "2_2") (pintype "passive"))
      (node (ref "U1") (pin "1") (pinfunction "PD3(INT1)_1") (pintype "bidirectional"))
    )
    (net (code "66") (name "TEMPO") (class "Default")
      (node (ref "R38") (pin "2") (pinfunction "2_2") (pintype "passive"))
      (node (ref "U1") (pin "19") (pinfunction "ADC6_19") (pintype "bidirectional"))
    )
    (net (code "67") (name "VCC") (class "Default")
      (node (ref "C7") (pin "+") (pinfunction "+_+") (pintype "passive"))
      (node (ref "D1") (pin "C") (pinfunction "C_C") (pintype "passive"))
      (node (ref "IC7") (pin "3") (pinfunction "VIN_3") (pintype "input"))
    )
    (net (code "68") (name "VEE") (class "Default")
      (node (ref "J9") (pin "1") (pinfunction "1_1") (pintype "passive"))
      (node (ref "J9") (pin "2") (pinfunction "2_2") (pintype "passive"))
      (node (ref "R41") (pin "1") (pinfunction "1_1") (pintype "passive"))
    )
    (net (code "69") (name "X_CV") (class "Default")
      (node (ref "C1") (pin "2") (pinfunction "2_2") (pintype "passive"))
      (node (ref "IC1") (pin "1") (pinfunction "OUT_1") (pintype "output"))
      (node (ref "R16") (pin "2") (pinfunction "2_2") (pintype "passive"))
      (node (ref "U1") (pin "23") (pinfunction "PC0(ADC0)_23") (pintype "bidirectional"))
    )
    (net (code "70") (name "Y_CV") (class "Default")
      (node (ref "C2") (pin "2") (pinfunction "2_2") (pintype "passive"))
      (node (ref "IC2") (pin "1") (pinfunction "OUT_1") (pintype "output"))
      (node (ref "R17") (pin "2") (pinfunction "2_2") (pintype "passive"))
      (node (ref "U1") (pin "24") (pinfunction "PC1(ADC1)_24") (pintype "bidirectional"))
    )
    (net (code "71") (name "unconnected-(IC8A-QH*-Pad9)") (class "Default")
      (node (ref "IC8") (pin "9") (pinfunction "QH*_9") (pintype "tri_state"))
    )
    (net (code "72") (name "unconnected-(J1-2-PadP2)") (class "Default")
      (node (ref "J1") (pin "P2") (pinfunction "2_P2") (pintype "bidirectional"))
    )
    (net (code "73") (name "unconnected-(J2-2-PadP2)") (class "Default")
      (node (ref "J2") (pin "P2") (pinfunction "2_P2") (pintype "bidirectional"))
    )
    (net (code "74") (name "unconnected-(J3-2-PadP2)") (class "Default")
      (node (ref "J3") (pin "P2") (pinfunction "2_P2") (pintype "bidirectional"))
    )
    (net (code "75") (name "unconnected-(J4-2-PadP2)") (class "Default")
      (node (ref "J4") (pin "P2") (pinfunction "2_P2") (pintype "bidirectional"))
    )
    (net (code "76") (name "unconnected-(J5-2-PadP2)") (class "Default")
      (node (ref "J5") (pin "P2") (pinfunction "2_P2") (pintype "bidirectional"))
    )
    (net (code "77") (name "unconnected-(J6-2-PadP2)") (class "Default")
      (node (ref "J6") (pin "P2") (pinfunction "2_P2") (pintype "bidirectional"))
    )
    (net (code "78") (name "unconnected-(J7-2-PadP2)") (class "Default")
      (node (ref "J7") (pin "P2") (pinfunction "2_P2") (pintype "bidirectional"))
    )
    (net (code "79") (name "unconnected-(J8-2-PadP2)") (class "Default")
      (node (ref "J8") (pin "P2") (pinfunction "2_P2") (pintype "bidirectional"))
    )
    (net (code "80") (name "unconnected-(J11-2-PadP2)") (class "Default")
      (node (ref "J11") (pin "P2") (pinfunction "2_P2") (pintype "bidirectional"))
    )
    (net (code "81") (name "unconnected-(J12-2-PadP2)") (class "Default")
      (node (ref "J12") (pin "P2") (pinfunction "2_P2") (pintype "bidirectional"))
    )
    (net (code "82") (name "unconnected-(J13-2-PadP2)") (class "Default")
      (node (ref "J13") (pin "P2") (pinfunction "2_P2") (pintype "bidirectional"))
    )
    (net (code "83") (name "unconnected-(J14-2-PadP2)") (class "Default")
      (node (ref "J14") (pin "P2") (pinfunction "2_P2") (pintype "bidirectional"))
    )
    (net (code "84") (name "unconnected-(J15-2-PadP2)") (class "Default")
      (node (ref "J15") (pin "P2") (pinfunction "2_P2") (pintype "bidirectional"))
    )
    (net (code "85") (name "unconnected-(J16-2-PadP2)") (class "Default")
      (node (ref "J16") (pin "P2") (pinfunction "2_P2") (pintype "bidirectional"))
    )
    (net (code "86") (name "unconnected-(U1-ADC7-Pad22)") (class "Default")
      (node (ref "U1") (pin "22") (pinfunction "ADC7_22") (pintype "bidirectional"))
    )
    (net (code "87") (name "unconnected-(U1-PB0(ICP)-Pad12)") (class "Default")
      (node (ref "U1") (pin "12") (pinfunction "PB0(ICP)_12") (pintype "bidirectional"))
    )
    (net (code "88") (name "unconnected-(U1-PB1(OC1A)-Pad13)") (class "Default")
      (node (ref "U1") (pin "13") (pinfunction "PB1(OC1A)_13") (pintype "bidirectional"))
    )
  )
)
